# SCH_Door_Lock_2022-08-30.net
KiCad netlist of a schematic drawn in EasyEDA
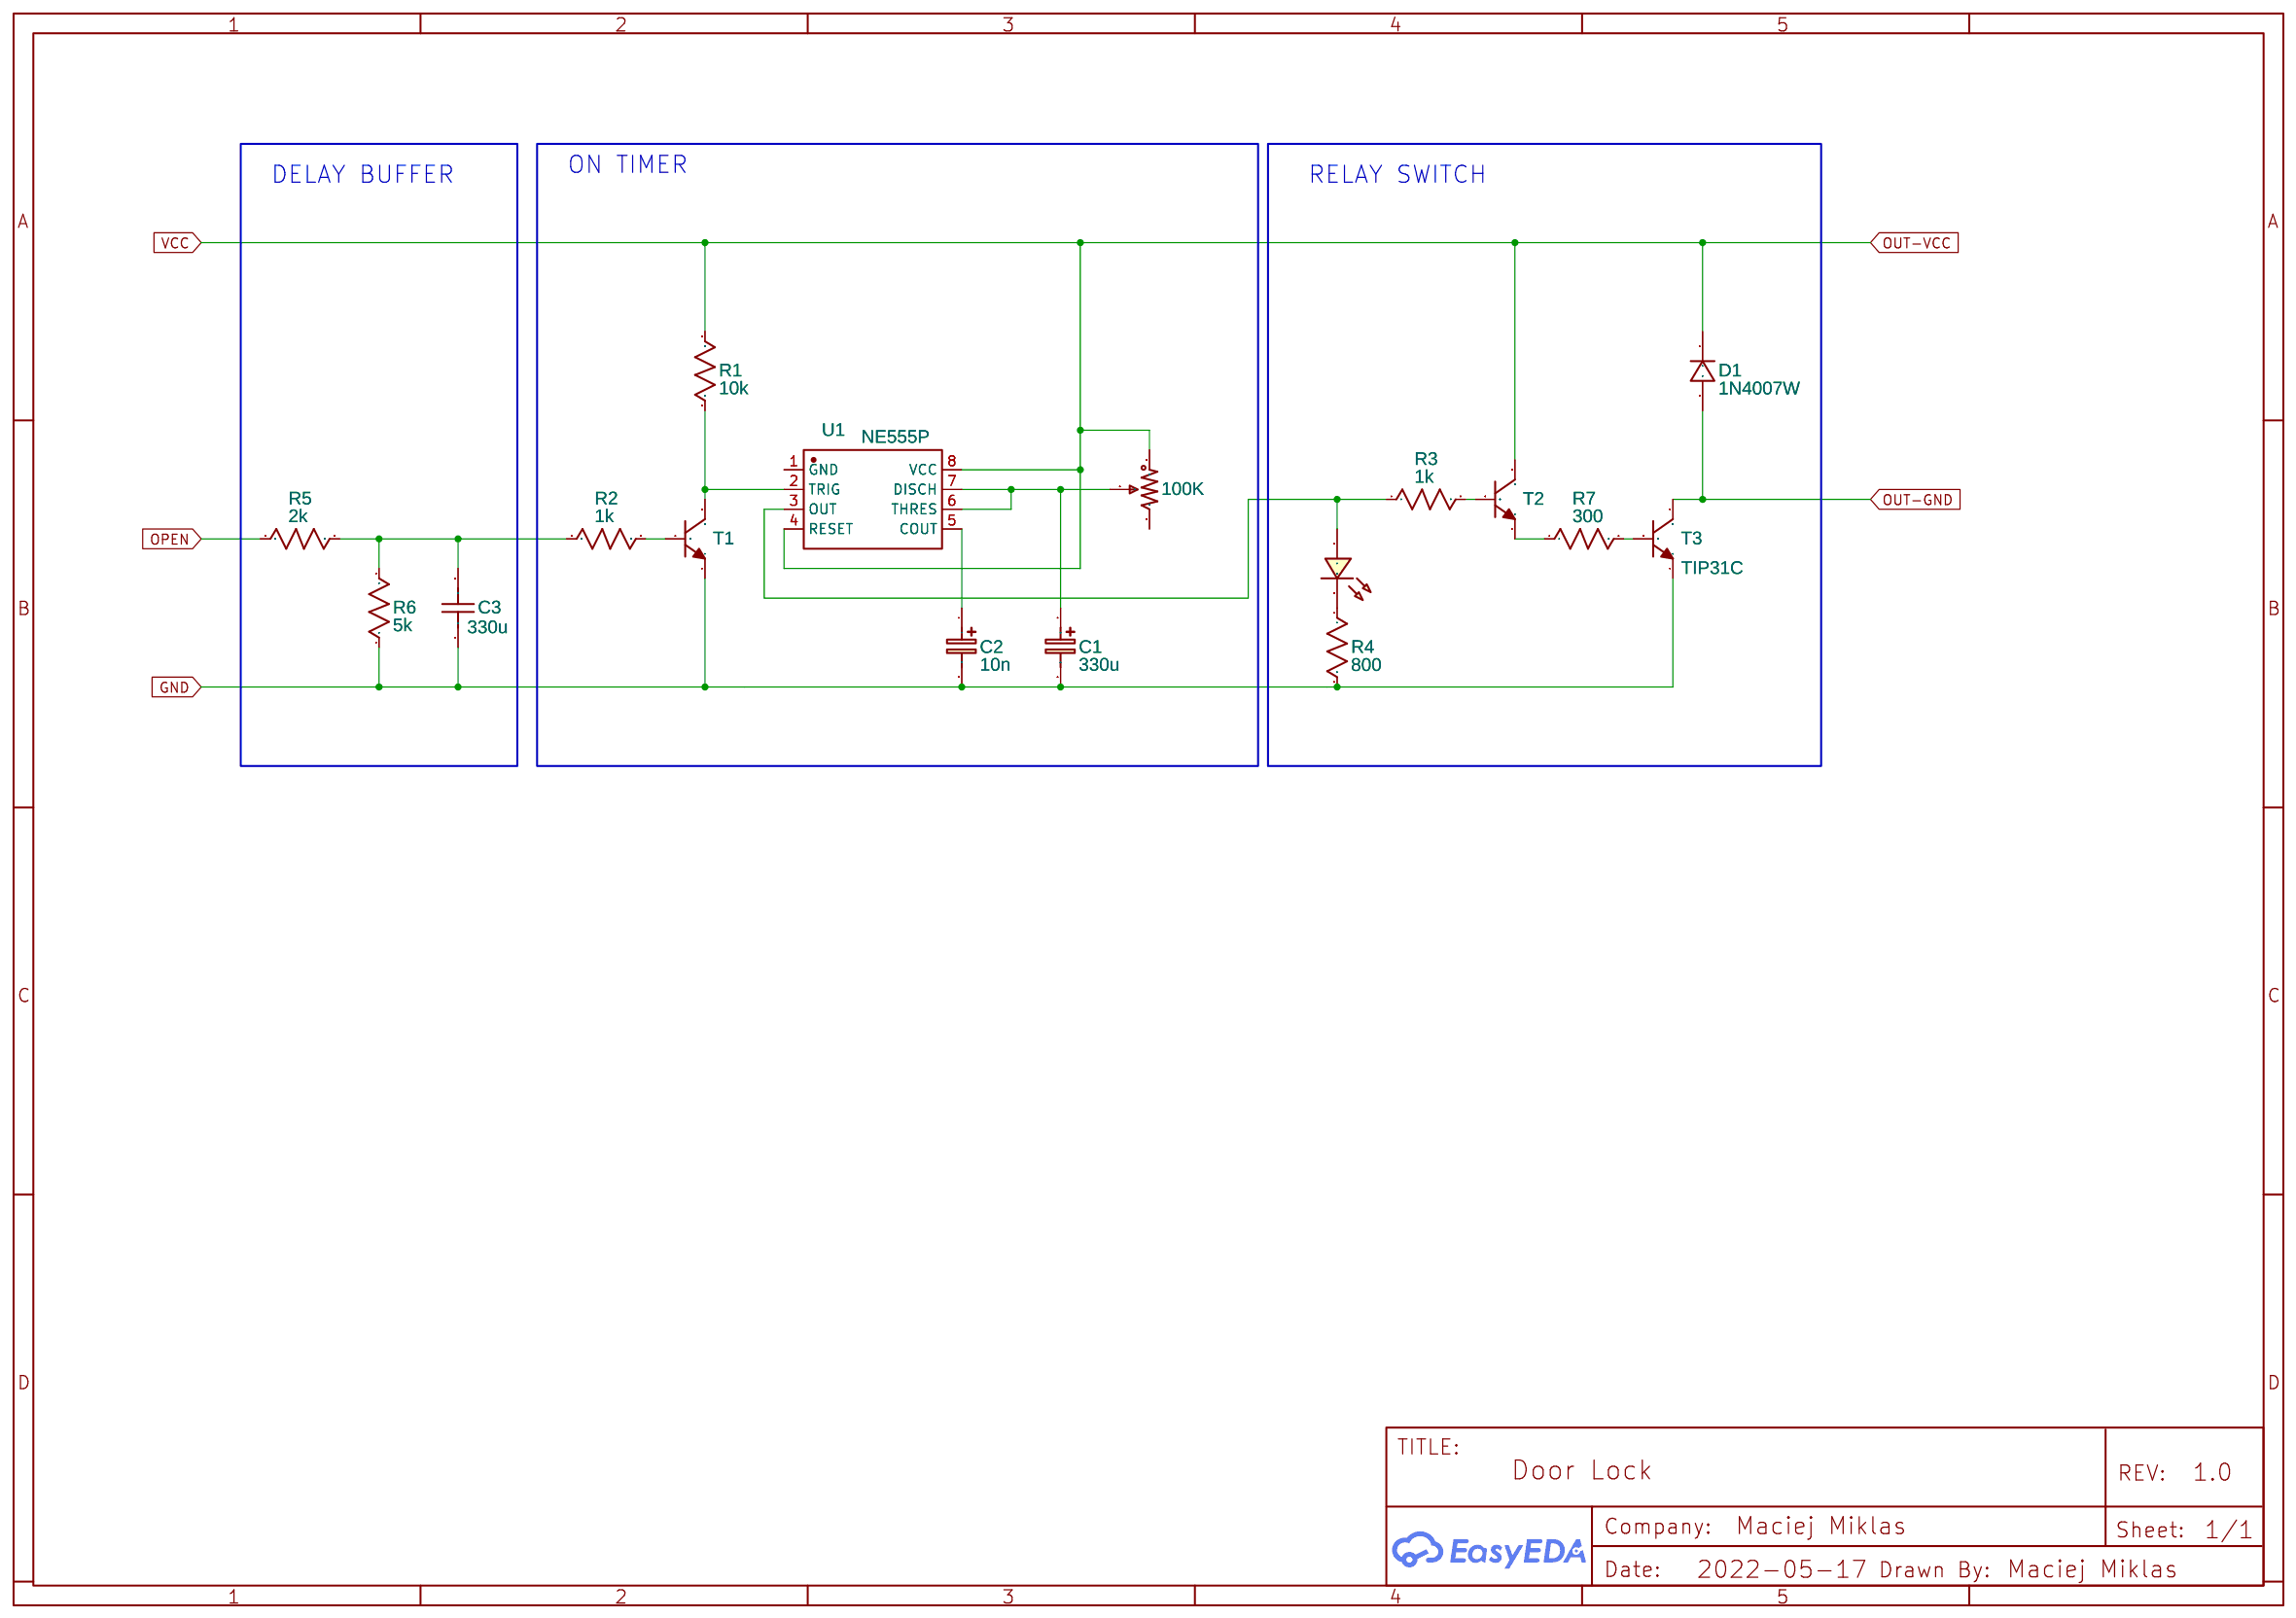
[diagram p0: schematic sheet]

(export (version "E")
  (design (tool "Eeschema 10.0.6"))
  (components
    (comp (ref "100K") (value "R_3386P_US") (libsource (lib "") (part "R_3386P_US")))
    (comp (ref "C1") (value "330u") (libsource (lib "") (part "C_Tan_SMD_A_EU_1")))
    (comp (ref "C2") (value "10n") (libsource (lib "") (part "C_Tan_SMD_A_EU")))
    (comp (ref "C3") (value "330u") (libsource (lib "") (part "C_0603_US")))
    (comp (ref "D1")
      (value "1N4007W")
      (fields (field (name "BOM_Supplier Part") "C328592"))
      (libsource (lib "") (part "1N4007W"))
    )
    (comp (ref "LED1")
      (value "LED-0603_R")
      (fields
        (field (name "BOM_Manufacturer Part") "19-217/R6C-AL1M2VY/3T")
        (field (name "BOM_Supplier Part") "C72044")
      )
      (libsource (lib "") (part "LED-0603_R"))
    )
    (comp (ref "R1") (value "10k") (libsource (lib "") (part "R_0603_US_2")))
    (comp (ref "R2") (value "1k") (libsource (lib "") (part "R_0603_US")))
    (comp (ref "R3") (value "1k") (libsource (lib "") (part "R_0603_US")))
    (comp (ref "R4") (value "800") (libsource (lib "") (part "R_0603_US_1")))
    (comp (ref "R5") (value "2k") (libsource (lib "") (part "R_0603_US")))
    (comp (ref "R6") (value "5k") (libsource (lib "") (part "R_0603_US_2")))
    (comp (ref "R7") (value "300") (libsource (lib "") (part "R_0603_US")))
    (comp (ref "T1")
      (value "2N3904(SOT-23)")
      (fields
        (field (name "BOM_Manufacturer Part") "2n3904S-RTK/PS")
        (field (name "BOM_Supplier Part") "C18536")
      )
      (libsource (lib "") (part "2N3904(SOT-23)"))
    )
    (comp (ref "T2")
      (value "2N3904(SOT-23)")
      (fields
        (field (name "BOM_Manufacturer Part") "2n3904S-RTK/PS")
        (field (name "BOM_Supplier Part") "C18536")
      )
      (libsource (lib "") (part "2N3904(SOT-23)"))
    )
    (comp (ref "T3")
      (value "TIP31C")
      (fields
        (field (name "BOM_Manufacturer Part") "2n3904S-RTK/PS")
        (field (name "BOM_Supplier Part") "C18536")
      )
      (libsource (lib "") (part "2N3904(SOT-23)"))
    )
    (comp (ref "U1")
      (value "NE555P")
      (fields (field (name "BOM_Supplier Part") "C46749"))
      (libsource (lib "") (part "NE555P"))
    )
  )
  (nets
    (net (code "1") (name "GND") (class "Default")
      (node (ref "C1") (pin "2") (pinfunction "2_2") (pintype "unspecified"))
      (node (ref "C2") (pin "2") (pinfunction "2_2") (pintype "unspecified"))
      (node (ref "C3") (pin "1") (pinfunction "1_1") (pintype "unspecified"))
      (node (ref "R4") (pin "2") (pinfunction "2_2") (pintype "unspecified"))
      (node (ref "R6") (pin "1") (pinfunction "1_1") (pintype "unspecified"))
      (node (ref "T1") (pin "1") (pinfunction "E_1") (pintype "input"))
      (node (ref "T3") (pin "1") (pinfunction "E_1") (pintype "input"))
    )
    (net (code "2") (name "Net-(C3-Pad2)") (class "Default")
      (node (ref "C3") (pin "2") (pinfunction "2_2") (pintype "unspecified"))
      (node (ref "R2") (pin "1") (pinfunction "1_1") (pintype "unspecified"))
      (node (ref "R5") (pin "2") (pinfunction "2_2") (pintype "unspecified"))
      (node (ref "R6") (pin "2") (pinfunction "2_2") (pintype "unspecified"))
    )
    (net (code "3") (name "Net-(LED1-Pad2)") (class "Default")
      (node (ref "LED1") (pin "2") (pinfunction "2_2") (pintype "unspecified"))
      (node (ref "R4") (pin "1") (pinfunction "1_1") (pintype "unspecified"))
    )
    (net (code "4") (name "Net-(T1-B)") (class "Default")
      (node (ref "R2") (pin "2") (pinfunction "2_2") (pintype "unspecified"))
      (node (ref "T1") (pin "2") (pinfunction "B_2") (pintype "input"))
    )
    (net (code "5") (name "Net-(T1-C)") (class "Default")
      (node (ref "R1") (pin "1") (pinfunction "1_1") (pintype "unspecified"))
      (node (ref "T1") (pin "3") (pinfunction "C_3") (pintype "input"))
      (node (ref "U1") (pin "2") (pinfunction "TRIG_2") (pintype "unspecified"))
    )
    (net (code "6") (name "Net-(T2-B)") (class "Default")
      (node (ref "R3") (pin "2") (pinfunction "2_2") (pintype "unspecified"))
      (node (ref "T2") (pin "2") (pinfunction "B_2") (pintype "input"))
    )
    (net (code "7") (name "Net-(T2-E)") (class "Default")
      (node (ref "R7") (pin "1") (pinfunction "1_1") (pintype "unspecified"))
      (node (ref "T2") (pin "1") (pinfunction "E_1") (pintype "input"))
    )
    (net (code "8") (name "Net-(T3-B)") (class "Default")
      (node (ref "R7") (pin "2") (pinfunction "2_2") (pintype "unspecified"))
      (node (ref "T3") (pin "2") (pinfunction "B_2") (pintype "input"))
    )
    (net (code "9") (name "Net-(U1-COUT)") (class "Default")
      (node (ref "C2") (pin "1") (pinfunction "1_1") (pintype "unspecified"))
      (node (ref "U1") (pin "5") (pinfunction "COUT_5") (pintype "unspecified"))
    )
    (net (code "10") (name "Net-(U1-DISCH)") (class "Default")
      (node (ref "100K") (pin "2") (pinfunction "2_2") (pintype "unspecified"))
      (node (ref "C1") (pin "1") (pinfunction "1_1") (pintype "unspecified"))
      (node (ref "U1") (pin "6") (pinfunction "THRES_6") (pintype "unspecified"))
      (node (ref "U1") (pin "7") (pinfunction "DISCH_7") (pintype "unspecified"))
    )
    (net (code "11") (name "Net-(U1-OUT)") (class "Default")
      (node (ref "LED1") (pin "1") (pinfunction "1_1") (pintype "unspecified"))
      (node (ref "R3") (pin "1") (pinfunction "1_1") (pintype "unspecified"))
      (node (ref "U1") (pin "3") (pinfunction "OUT_3") (pintype "unspecified"))
    )
    (net (code "12") (name "OPEN") (class "Default")
      (node (ref "R5") (pin "1") (pinfunction "1_1") (pintype "unspecified"))
    )
    (net (code "13") (name "OUT-GND") (class "Default")
      (node (ref "D1") (pin "2") (pinfunction "2_2") (pintype "unspecified"))
      (node (ref "T3") (pin "3") (pinfunction "C_3") (pintype "input"))
    )
    (net (code "14") (name "OUT-VCC") (class "Default")
      (node (ref "100K") (pin "1") (pinfunction "1_1") (pintype "unspecified"))
      (node (ref "D1") (pin "1") (pinfunction "1_1") (pintype "unspecified"))
      (node (ref "R1") (pin "2") (pinfunction "2_2") (pintype "unspecified"))
      (node (ref "T2") (pin "3") (pinfunction "C_3") (pintype "input"))
      (node (ref "U1") (pin "4") (pinfunction "RESET_4") (pintype "unspecified"))
      (node (ref "U1") (pin "8") (pinfunction "VCC_8") (pintype "unspecified"))
    )
    (net (code "15") (name "unconnected-(100K-Pad3)") (class "Default")
      (node (ref "100K") (pin "3") (pinfunction "3_3") (pintype "unspecified"))
    )
    (net (code "16") (name "unconnected-(U1-GND-Pad1)") (class "Default")
      (node (ref "U1") (pin "1") (pinfunction "GND_1") (pintype "unspecified"))
    )
  )
)
